# GatewayLoRa0.net
KiCad netlist of a schematic drawn in Altium Designer
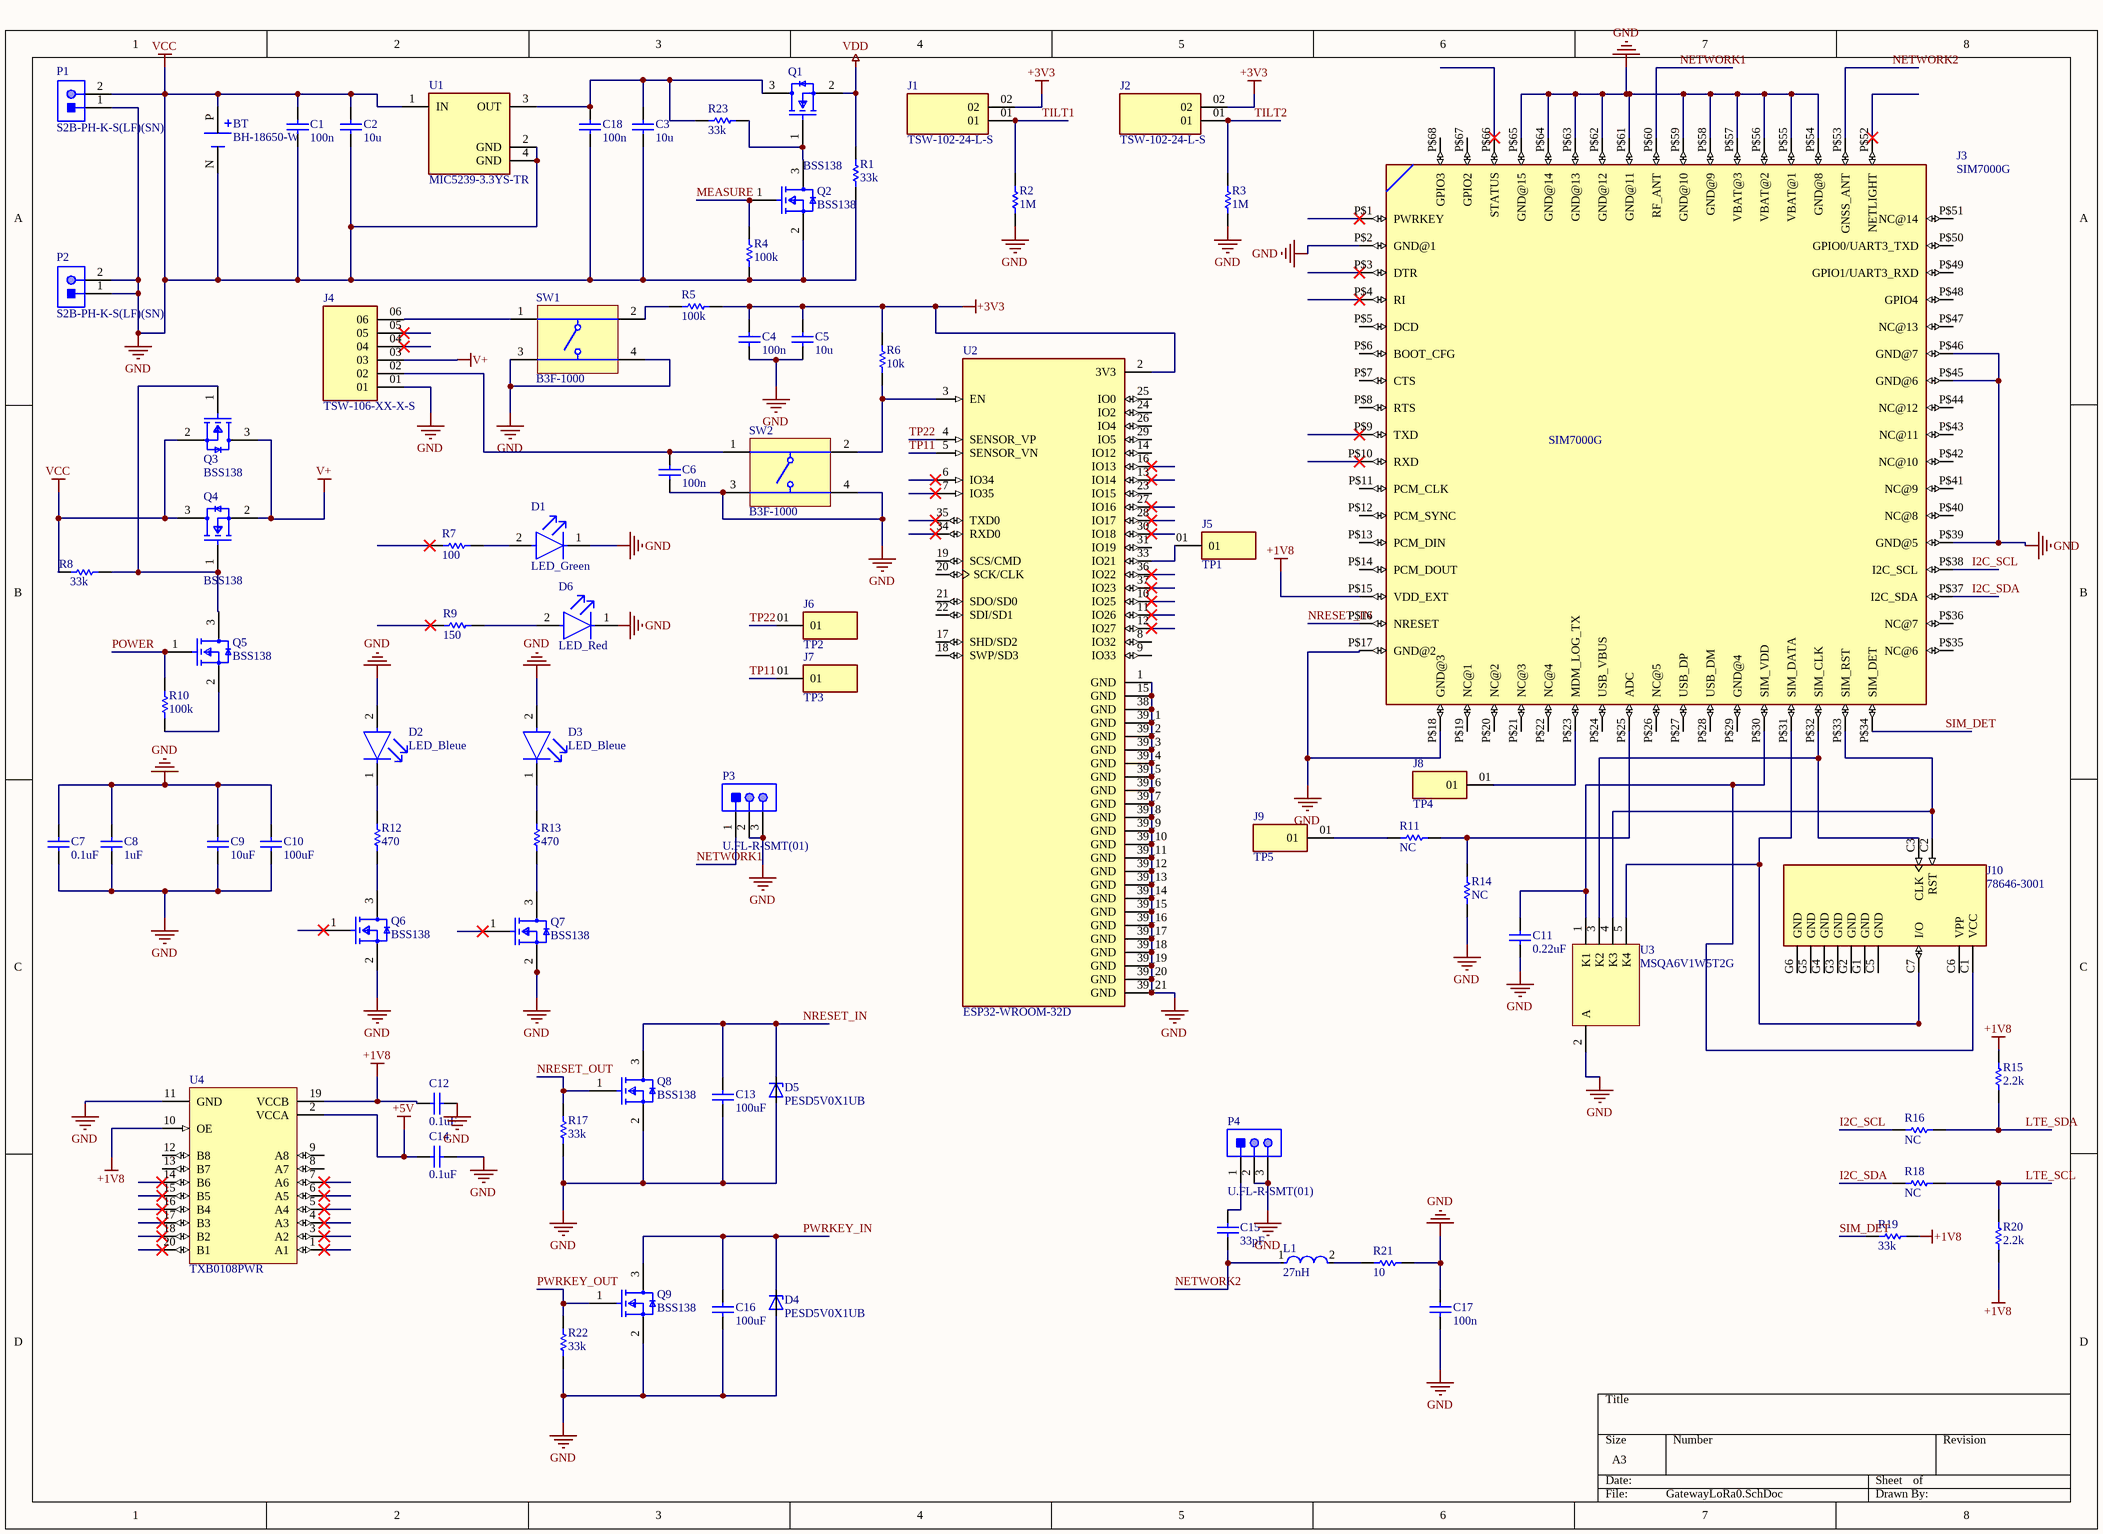
[diagram p0: GatewayLoRa0.SchDoc]

(export (version "E")
  (design (tool "Eeschema 10.0.6"))
  (components
    (comp (ref "BT")
      (value "BH-18650-W")
      (footprint "BAT_BH-18650-W")
      (description "BATTERY HOLDER 18650 6 LEADS")
      (fields (field (name "MF") "MPD"))
      (libsource (lib "BH-18650-W") (part "BH-18650-W"))
    )
    (comp (ref "C1")
      (value "100n")
      (footprint "CAPC1210(3225)280_L")
      (description "CAP 22uF 10V ±10% 1210 (3225 Metric) Thickness 2.8mm SMD")
      (fields (field (name "TOLERANCE") "Â±10%"))
      (libsource (lib "Altium Content Vault") (part "CAP"))
    )
    (comp (ref "C2")
      (value "10u")
      (footprint "CAPC1210(3225)280_L")
      (description "CAP 22uF 10V ±10% 1210 (3225 Metric) Thickness 2.8mm SMD")
      (fields (field (name "TOLERANCE") "Â±10%"))
      (libsource (lib "Altium Content Vault") (part "CAP"))
    )
    (comp (ref "C3")
      (value "10u")
      (footprint "CAPC1210(3225)280_L")
      (description "CAP 22uF 10V ±10% 1210 (3225 Metric) Thickness 2.8mm SMD")
      (fields (field (name "TOLERANCE") "Â±10%"))
      (libsource (lib "Altium Content Vault") (part "CAP"))
    )
    (comp (ref "C4")
      (value "100n")
      (footprint "CAPC1210(3225)280_L")
      (description "CAP 22uF 10V ±10% 1210 (3225 Metric) Thickness 2.8mm SMD")
      (fields (field (name "TOLERANCE") "Â±10%"))
      (libsource (lib "Altium Content Vault") (part "CAP"))
    )
    (comp (ref "C5")
      (value "10u")
      (footprint "CAPC1210(3225)280_L")
      (description "CAP 22uF 10V ±10% 1210 (3225 Metric) Thickness 2.8mm SMD")
      (fields (field (name "TOLERANCE") "Â±10%"))
      (libsource (lib "Altium Content Vault") (part "CAP"))
    )
    (comp (ref "C6")
      (value "100n")
      (footprint "CAPC1210(3225)280_L")
      (description "CAP 22uF 10V ±10% 1210 (3225 Metric) Thickness 2.8mm SMD")
      (fields (field (name "TOLERANCE") "Â±10%"))
      (libsource (lib "Altium Content Vault") (part "CAP"))
    )
    (comp (ref "C7")
      (value "0.1uF")
      (footprint "CAPC1210(3225)280_L")
      (description "CAP 22uF 10V ±10% 1210 (3225 Metric) Thickness 2.8mm SMD")
      (fields (field (name "TOLERANCE") "Â±10%"))
      (libsource (lib "Altium Content Vault") (part "CAP"))
    )
    (comp (ref "C8")
      (value "1uF")
      (footprint "CAPC1210(3225)280_L")
      (description "CAP 22uF 10V ±10% 1210 (3225 Metric) Thickness 2.8mm SMD")
      (fields (field (name "TOLERANCE") "Â±10%"))
      (libsource (lib "Altium Content Vault") (part "CAP"))
    )
    (comp (ref "C9")
      (value "10uF")
      (footprint "CAPC1210(3225)280_L")
      (description "CAP 22uF 10V ±10% 1210 (3225 Metric) Thickness 2.8mm SMD")
      (fields (field (name "TOLERANCE") "Â±10%"))
      (libsource (lib "Altium Content Vault") (part "CAP"))
    )
    (comp (ref "C10")
      (value "100uF")
      (footprint "CAPC1210(3225)280_L")
      (description "CAP 22uF 10V ±10% 1210 (3225 Metric) Thickness 2.8mm SMD")
      (fields (field (name "TOLERANCE") "Â±10%"))
      (libsource (lib "Altium Content Vault") (part "CAP"))
    )
    (comp (ref "C11")
      (value "0.22uF")
      (footprint "CAPC1210(3225)280_L")
      (description "CAP 22uF 10V ±10% 1210 (3225 Metric) Thickness 2.8mm SMD")
      (fields (field (name "TOLERANCE") "Â±10%"))
      (libsource (lib "Altium Content Vault") (part "CAP"))
    )
    (comp (ref "C12")
      (value "0.1uF")
      (footprint "CAPC1210(3225)280_L")
      (description "CAP 22uF 10V ±10% 1210 (3225 Metric) Thickness 2.8mm SMD")
      (fields (field (name "TOLERANCE") "Â±10%"))
      (libsource (lib "Altium Content Vault") (part "CAP"))
    )
    (comp (ref "C13")
      (value "100uF")
      (footprint "CAPC1210(3225)280_L")
      (description "CAP 22uF 10V ±10% 1210 (3225 Metric) Thickness 2.8mm SMD")
      (fields (field (name "TOLERANCE") "Â±10%"))
      (libsource (lib "Altium Content Vault") (part "CAP"))
    )
    (comp (ref "C14")
      (value "0.1uF")
      (footprint "CAPC1210(3225)280_L")
      (description "CAP 22uF 10V ±10% 1210 (3225 Metric) Thickness 2.8mm SMD")
      (fields (field (name "TOLERANCE") "Â±10%"))
      (libsource (lib "Altium Content Vault") (part "CAP"))
    )
    (comp (ref "C15")
      (value "33pF")
      (footprint "CAPC1210(3225)280_L")
      (description "CAP 22uF 10V ±10% 1210 (3225 Metric) Thickness 2.8mm SMD")
      (fields (field (name "TOLERANCE") "Â±10%"))
      (libsource (lib "Altium Content Vault") (part "CAP"))
    )
    (comp (ref "C16")
      (value "100uF")
      (footprint "CAPC1210(3225)280_L")
      (description "CAP 22uF 10V ±10% 1210 (3225 Metric) Thickness 2.8mm SMD")
      (fields (field (name "TOLERANCE") "Â±10%"))
      (libsource (lib "Altium Content Vault") (part "CAP"))
    )
    (comp (ref "C17")
      (value "100n")
      (footprint "CAPC1210(3225)280_L")
      (description "CAP 22uF 10V ±10% 1210 (3225 Metric) Thickness 2.8mm SMD")
      (fields (field (name "TOLERANCE") "Â±10%"))
      (libsource (lib "Altium Content Vault") (part "CAP"))
    )
    (comp (ref "C18")
      (value "100n")
      (footprint "CAPC1210(3225)280_L")
      (description "CAP 22uF 10V ±10% 1210 (3225 Metric) Thickness 2.8mm SMD")
      (fields (field (name "TOLERANCE") "Â±10%"))
      (libsource (lib "Altium Content Vault") (part "CAP"))
    )
    (comp (ref "D1")
      (value "LED_Green")
      (footprint "FP-LTST-C191KGKT-MFG")
      (description "LED GREEN CLEAR SMD")
      (libsource (lib "Altium Content Vault") (part "8706943c75ba83719d021d2fdc84c58"))
    )
    (comp (ref "D2")
      (value "LED_Bleue")
      (footprint "FP-LTST-C193TBKT-5A-MFG")
      (description "LED BLUE CLEAR CHIP SMD")
      (libsource (lib "Altium Content Vault") (part "8706943c75ba83719d021d2fdc84c58"))
    )
    (comp (ref "D3")
      (value "LED_Bleue")
      (footprint "FP-LTST-C193TBKT-5A-MFG")
      (description "LED BLUE CLEAR CHIP SMD")
      (libsource (lib "Altium Content Vault") (part "8706943c75ba83719d021d2fdc84c58"))
    )
    (comp (ref "D4")
      (value "PESD5V0X1UB")
      (footprint "SOD523")
      (description "8V _Typ_ Clamp 1.5A _8/20Âµs_ Ipp Tvs Diode Surface Mount SOD-523")
      (fields (field (name "MF") "NXP Semiconductors"))
      (libsource (lib "PESD5V0X1UB") (part "PESD5V0X1UB"))
    )
    (comp (ref "D5")
      (value "PESD5V0X1UB")
      (footprint "SOD523")
      (description "8V _Typ_ Clamp 1.5A _8/20Âµs_ Ipp Tvs Diode Surface Mount SOD-523")
      (fields (field (name "MF") "NXP Semiconductors"))
      (libsource (lib "PESD5V0X1UB") (part "PESD5V0X1UB"))
    )
    (comp (ref "D6")
      (value "LED_Red")
      (footprint "FP-SML-P11UTT86-MFG")
      (description "LED RED CLEAR 1006 SMD")
      (libsource (lib "Altium Content Vault") (part "8706943c75ba83719d021d2fdc84c58"))
    )
    (comp (ref "J1")
      (value "TSW-102-24-L-S")
      (footprint "SAMTEC_TSW-102-24-L-S")
      (description "Connector Header Through Hole 2 position 0.100 (2.54mm)")
      (fields (field (name "MF") "Samtec"))
      (libsource (lib "TSW-102-24-L-S") (part "TSW-102-24-L-S"))
    )
    (comp (ref "J2")
      (value "TSW-102-24-L-S")
      (footprint "SAMTEC_TSW-102-24-L-S")
      (description "Connector Header Through Hole 2 position 0.100 (2.54mm)")
      (fields (field (name "MF") "Samtec"))
      (libsource (lib "TSW-102-24-L-S") (part "TSW-102-24-L-S"))
    )
    (comp (ref "J3")
      (value "SIM7000G")
      (footprint "SIM7000G")
      (fields (field (name "MF") "SIMCom Wireless Solutions Limited"))
      (libsource (lib "SIM7000G") (part "SIM7000G"))
    )
    (comp (ref "J4")
      (value "TSW-106-XX-X-S")
      (footprint "SAMTEC_TSW-106-XX-X-S")
      (description "TSW - Samtec 2.54mm Pin Header 10.92mm Overall Pin Length (07) - Fast Stock")
      (fields (field (name "MF") "Samtec Inc."))
      (libsource (lib "TSW-106-XX-X-S") (part "TSW-106-XX-X-S"))
    )
    (comp (ref "J5")
      (value "TP1")
      (footprint "SAMTEC_TSW-101-07-L-S")
      (fields (field (name "MF") "Samtec Inc.") (field (name "MP") "TSW-101-07-L-S"))
      (libsource (lib "TSW-101-07-L-S") (part "TSW-101-07-L-S"))
    )
    (comp (ref "J6")
      (value "TP2")
      (footprint "SAMTEC_TSW-101-07-L-S")
      (fields (field (name "MF") "Samtec Inc.") (field (name "MP") "TSW-101-07-L-S"))
      (libsource (lib "TSW-101-07-L-S") (part "TSW-101-07-L-S"))
    )
    (comp (ref "J7")
      (value "TP3")
      (footprint "SAMTEC_TSW-101-07-L-S")
      (fields (field (name "MF") "Samtec Inc.") (field (name "MP") "TSW-101-07-L-S"))
      (libsource (lib "TSW-101-07-L-S") (part "TSW-101-07-L-S"))
    )
    (comp (ref "J8")
      (value "TP4")
      (footprint "SAMTEC_TSW-101-07-L-S")
      (fields (field (name "MF") "Samtec Inc.") (field (name "MP") "TSW-101-07-L-S"))
      (libsource (lib "") (part "TSW-101-07-L-S_1"))
    )
    (comp (ref "J9")
      (value "TP5")
      (footprint "SAMTEC_TSW-101-07-L-S")
      (fields (field (name "MF") "Samtec Inc.") (field (name "MP") "TSW-101-07-L-S"))
      (libsource (lib "") (part "TSW-101-07-L-S_1"))
    )
    (comp (ref "J10")
      (value "78646-3001")
      (footprint "MOLEX_78646-3001")
      (description "6 Position Card Connector Micro SIM Surface Mount, Right Angle Gold")
      (fields (field (name "MF") "Molex"))
      (libsource (lib "78646-3001") (part "78646-3001"))
    )
    (comp (ref "L1")
      (value "27nH")
      (footprint "FP-LQM21PH_G0-IPC_C")
      (description "Multilayer Type Inductor for Power Lines, 0805 (2012), 1μH, 30%, 0.0825Ω, 1.3A")
      (fields (field (name "TOLERANCE") "30%"))
      (libsource (lib "Altium Content Vault") (part "725321dda6339637d4d059423bc1c3c"))
    )
    (comp (ref "P1")
      (value "S2B-PH-K-S(LF)(SN)")
      (footprint "JST-S2B-PH-K-S_V")
      (fields (field (name "TOLERANCE") "20%"))
      (libsource (lib "Altium Content Vault") (part "CN-1P-M-R2"))
    )
    (comp (ref "P2")
      (value "S2B-PH-K-S(LF)(SN)")
      (footprint "JST-S2B-PH-K-S_V")
      (fields (field (name "TOLERANCE") "20%"))
      (libsource (lib "Altium Content Vault") (part "CN-1P-M-R2"))
    )
    (comp (ref "P3")
      (value "U.FL-R-SMT(01)")
      (footprint "HRS-U.FL-R-SMT(10)_V")
      (description "CONN RECPT ULTRA-MINI COAX SMD")
      (fields (field (name "MANUFACTURER") "Hirose Electric") (field (name "APPROVAL CATEGORY") "UL94V-0"))
      (libsource (lib "Altium Content Vault") (part "CN-1P-M-R3"))
    )
    (comp (ref "P4")
      (value "U.FL-R-SMT(01)")
      (footprint "HRS-U.FL-R-SMT(10)_V")
      (description "CONN RECPT ULTRA-MINI COAX SMD")
      (fields (field (name "MANUFACTURER") "Hirose Electric") (field (name "APPROVAL CATEGORY") "UL94V-0"))
      (libsource (lib "Altium Content Vault") (part "CN-1P-M-R3"))
    )
    (comp (ref "Q1")
      (value "BSS138")
      (footprint "FP-318-08-IPC_B")
      (description "MOSFET N-CH 50V 220MA SOT-23")
      (libsource (lib "Altium Content Vault") (part "3b9c635fedb024a5347a57b145af9cc"))
    )
    (comp (ref "Q2")
      (value "BSS138")
      (footprint "FP-318-08-IPC_B")
      (description "MOSFET N-CH 50V 220MA SOT-23")
      (libsource (lib "Altium Content Vault") (part "3b9c635fedb024a5347a57b145af9cc"))
    )
    (comp (ref "Q3")
      (value "BSS138")
      (footprint "FP-318-08-IPC_B")
      (description "MOSFET N-CH 50V 220MA SOT-23")
      (libsource (lib "Altium Content Vault") (part "3b9c635fedb024a5347a57b145af9cc"))
    )
    (comp (ref "Q4")
      (value "BSS138")
      (footprint "FP-318-08-IPC_B")
      (description "MOSFET N-CH 50V 220MA SOT-23")
      (libsource (lib "Altium Content Vault") (part "3b9c635fedb024a5347a57b145af9cc"))
    )
    (comp (ref "Q5")
      (value "BSS138")
      (footprint "FP-318-08-IPC_B")
      (description "MOSFET N-CH 50V 220MA SOT-23")
      (libsource (lib "Altium Content Vault") (part "3b9c635fedb024a5347a57b145af9cc"))
    )
    (comp (ref "Q6")
      (value "BSS138")
      (footprint "FP-318-08-IPC_B")
      (description "MOSFET N-CH 50V 220MA SOT-23")
      (libsource (lib "Altium Content Vault") (part "3b9c635fedb024a5347a57b145af9cc"))
    )
    (comp (ref "Q7")
      (value "BSS138")
      (footprint "FP-318-08-IPC_B")
      (description "MOSFET N-CH 50V 220MA SOT-23")
      (libsource (lib "Altium Content Vault") (part "3b9c635fedb024a5347a57b145af9cc"))
    )
    (comp (ref "Q8")
      (value "BSS138")
      (footprint "FP-318-08-IPC_B")
      (description "MOSFET N-CH 50V 220MA SOT-23")
      (libsource (lib "Altium Content Vault") (part "3b9c635fedb024a5347a57b145af9cc"))
    )
    (comp (ref "Q9")
      (value "BSS138")
      (footprint "FP-318-08-IPC_B")
      (description "MOSFET N-CH 50V 220MA SOT-23")
      (libsource (lib "Altium Content Vault") (part "3b9c635fedb024a5347a57b145af9cc"))
    )
    (comp (ref "R1")
      (value "33k")
      (footprint "RESC3216X60X45LL10T20")
      (fields (field (name "MANUFACTURER") "Vishay Dale") (field (name "PART NUMBER") "CRCW120651R0FKEA"))
      (libsource (lib "Altium Content Vault") (part "RES"))
    )
    (comp (ref "R2")
      (value "1M")
      (footprint "RESC3216X60X45LL10T20")
      (fields (field (name "MANUFACTURER") "Vishay Dale") (field (name "PART NUMBER") "CRCW120651R0FKEA"))
      (libsource (lib "Altium Content Vault") (part "RES"))
    )
    (comp (ref "R3")
      (value "1M")
      (footprint "RESC3216X60X45LL10T20")
      (fields (field (name "MANUFACTURER") "Vishay Dale") (field (name "PART NUMBER") "CRCW120651R0FKEA"))
      (libsource (lib "Altium Content Vault") (part "RES"))
    )
    (comp (ref "R4")
      (value "100k")
      (footprint "RESC3216X60X45LL10T20")
      (fields (field (name "MANUFACTURER") "Vishay Dale") (field (name "PART NUMBER") "CRCW120651R0FKEA"))
      (libsource (lib "Altium Content Vault") (part "RES"))
    )
    (comp (ref "R5")
      (value "100k")
      (footprint "RESC3216X60X45LL10T20")
      (fields (field (name "MANUFACTURER") "Vishay Dale") (field (name "PART NUMBER") "CRCW120651R0FKEA"))
      (libsource (lib "Altium Content Vault") (part "RES"))
    )
    (comp (ref "R6")
      (value "10k")
      (footprint "RESC3216X60X45LL10T20")
      (fields (field (name "MANUFACTURER") "Vishay Dale") (field (name "PART NUMBER") "CRCW120651R0FKEA"))
      (libsource (lib "Altium Content Vault") (part "RES"))
    )
    (comp (ref "R7")
      (value "100")
      (footprint "RESC3216X60X45LL10T20")
      (fields (field (name "MANUFACTURER") "Vishay Dale") (field (name "PART NUMBER") "CRCW120651R0FKEA"))
      (libsource (lib "Altium Content Vault") (part "RES"))
    )
    (comp (ref "R8")
      (value "33k")
      (footprint "RESC3216X60X45LL10T20")
      (fields (field (name "MANUFACTURER") "Vishay Dale") (field (name "PART NUMBER") "CRCW120651R0FKEA"))
      (libsource (lib "Altium Content Vault") (part "RES"))
    )
    (comp (ref "R9")
      (value "150")
      (footprint "RESC3216X60X45LL10T20")
      (fields (field (name "MANUFACTURER") "Vishay Dale") (field (name "PART NUMBER") "CRCW120651R0FKEA"))
      (libsource (lib "Altium Content Vault") (part "RES"))
    )
    (comp (ref "R10")
      (value "100k")
      (footprint "RESC3216X60X45LL10T20")
      (fields (field (name "MANUFACTURER") "Vishay Dale") (field (name "PART NUMBER") "CRCW120651R0FKEA"))
      (libsource (lib "Altium Content Vault") (part "RES"))
    )
    (comp (ref "R11")
      (value "NC")
      (footprint "RESC3216X60X45LL10T20")
      (fields (field (name "MANUFACTURER") "Vishay Dale") (field (name "PART NUMBER") "CRCW120651R0FKEA"))
      (libsource (lib "Altium Content Vault") (part "RES"))
    )
    (comp (ref "R12")
      (value "470")
      (footprint "RESC3216X60X45LL10T20")
      (fields (field (name "MANUFACTURER") "Vishay Dale") (field (name "PART NUMBER") "CRCW120651R0FKEA"))
      (libsource (lib "Altium Content Vault") (part "RES"))
    )
    (comp (ref "R13")
      (value "470")
      (footprint "RESC3216X60X45LL10T20")
      (fields (field (name "MANUFACTURER") "Vishay Dale") (field (name "PART NUMBER") "CRCW120651R0FKEA"))
      (libsource (lib "Altium Content Vault") (part "RES"))
    )
    (comp (ref "R14")
      (value "NC")
      (footprint "RESC3216X60X45LL10T20")
      (fields (field (name "MANUFACTURER") "Vishay Dale") (field (name "PART NUMBER") "CRCW120651R0FKEA"))
      (libsource (lib "Altium Content Vault") (part "RES"))
    )
    (comp (ref "R15")
      (value "2.2k")
      (footprint "RESC3216X60X45LL10T20")
      (fields (field (name "MANUFACTURER") "Vishay Dale") (field (name "PART NUMBER") "CRCW120651R0FKEA"))
      (libsource (lib "Altium Content Vault") (part "RES"))
    )
    (comp (ref "R16")
      (value "NC")
      (footprint "RESC3216X60X45LL10T20")
      (fields (field (name "MANUFACTURER") "Vishay Dale") (field (name "PART NUMBER") "CRCW120651R0FKEA"))
      (libsource (lib "Altium Content Vault") (part "RES"))
    )
    (comp (ref "R17")
      (value "33k")
      (footprint "RESC3216X60X45LL10T20")
      (fields (field (name "MANUFACTURER") "Vishay Dale") (field (name "PART NUMBER") "CRCW120651R0FKEA"))
      (libsource (lib "Altium Content Vault") (part "RES"))
    )
    (comp (ref "R18")
      (value "NC")
      (footprint "RESC3216X60X45LL10T20")
      (fields (field (name "MANUFACTURER") "Vishay Dale") (field (name "PART NUMBER") "CRCW120651R0FKEA"))
      (libsource (lib "Altium Content Vault") (part "RES"))
    )
    (comp (ref "R19")
      (value "33k")
      (footprint "RESC3216X60X45LL10T20")
      (fields (field (name "MANUFACTURER") "Vishay Dale") (field (name "PART NUMBER") "CRCW120651R0FKEA"))
      (libsource (lib "Altium Content Vault") (part "RES"))
    )
    (comp (ref "R20")
      (value "2.2k")
      (footprint "RESC3216X60X45LL10T20")
      (fields (field (name "MANUFACTURER") "Vishay Dale") (field (name "PART NUMBER") "CRCW120651R0FKEA"))
      (libsource (lib "Altium Content Vault") (part "RES"))
    )
    (comp (ref "R21")
      (value "10")
      (footprint "RESC3216X60X45LL10T20")
      (fields (field (name "MANUFACTURER") "Vishay Dale") (field (name "PART NUMBER") "CRCW120651R0FKEA"))
      (libsource (lib "Altium Content Vault") (part "RES"))
    )
    (comp (ref "R22")
      (value "33k")
      (footprint "RESC3216X60X45LL10T20")
      (fields (field (name "MANUFACTURER") "Vishay Dale") (field (name "PART NUMBER") "CRCW120651R0FKEA"))
      (libsource (lib "Altium Content Vault") (part "RES"))
    )
    (comp (ref "R23")
      (value "33k")
      (footprint "RESC3216X60X45LL10T20")
      (fields (field (name "MANUFACTURER") "Vishay Dale") (field (name "PART NUMBER") "CRCW120651R0FKEA"))
      (libsource (lib "Altium Content Vault") (part "RES"))
    )
    (comp (ref "SW1")
      (value "B3F-1000")
      (footprint "OMRON-B3F-1000-4_V")
      (description "Tactile Switch, SPST-NO, 0.05 A, 5 to 24 V, -25 to 70 degC, 4-Pin THD, RoHS, Bulk")
      (libsource (lib "Altium Content Vault") (part "SW-SPST-4_A"))
    )
    (comp (ref "SW2")
      (value "B3F-1000")
      (footprint "OMRON-B3F-1000-4_V")
      (description "Tactile Switch, SPST-NO, 0.05 A, 5 to 24 V, -25 to 70 degC, 4-Pin THD, RoHS, Bulk")
      (libsource (lib "Altium Content Vault") (part "SW-SPST-4_A"))
    )
    (comp (ref "U1")
      (value "MIC5239-3.3YS-TR")
      (footprint "FP-SOT223-3LD-PL-1-MFG")
      (description "IC REG LINEAR 3.3V 500MA SOT223")
      (fields
        (field (name "OCTOPART") "https://octopart.com/mic5239-3.3ys-tr-microchip-66802369")
        (field (name "MANUFACTURER") "Microchip")
      )
      (libsource (lib "Altium Content Vault") (part "ef58ecf1460df94932fa90dd3618f80"))
    )
    (comp (ref "U2")
      (value "ESP32-WROOM-32D")
      (footprint "MODULE_ESP32-WROOM-32D")
      (fields (field (name "MF") "Espressif Systems"))
      (libsource (lib "ESP32-WROOM-32D") (part "ESP32-WROOM-32D"))
    )
    (comp (ref "U3")
      (value "MSQA6V1W5T2G")
      (footprint "ONSC-SC70-5-419A-02_V")
      (description "Quad Array ESD Protection Diodes with Low Clamping Voltage, 5-Pin SC70, Pb-Free, Tape and Reel")
      (fields (field (name "MANUFACTURER") "On Semiconductor"))
      (libsource (lib "Altium Content Vault") (part "ONSC-K1A2K3K4K5-5"))
    )
    (comp (ref "U4")
      (value "TXB0108PWR")
      (footprint "PW0020A_L")
      (fields (field (name "MANUFACTURER") "Texas Instruments"))
      (libsource (lib "Altium Content Vault") (part "TI-TXB0108-PW-20"))
    )
  )
  (nets
    (net (code "1") (name "+1V8") (class "Default")
      (node (ref "C12") (pin "2") (pinfunction "2_2") (pintype "passive"))
      (node (ref "J3") (pin "P$15") (pinfunction "VDD_EXT_P$15") (pintype "bidirectional"))
      (node (ref "R15") (pin "2") (pinfunction "2_2") (pintype "passive"))
      (node (ref "R19") (pin "2") (pinfunction "2_2") (pintype "passive"))
      (node (ref "R20") (pin "1") (pinfunction "1_1") (pintype "passive"))
      (node (ref "U4") (pin "10") (pinfunction "OE_10") (pintype "input"))
      (node (ref "U4") (pin "19") (pinfunction "VCCB_19") (pintype "power_in"))
    )
    (net (code "2") (name "+3V3") (class "Default")
      (node (ref "C4") (pin "2") (pinfunction "2_2") (pintype "passive"))
      (node (ref "C5") (pin "2") (pinfunction "2_2") (pintype "passive"))
      (node (ref "J1") (pin "02") (pinfunction "02_02") (pintype "passive"))
      (node (ref "J2") (pin "02") (pinfunction "02_02") (pintype "passive"))
      (node (ref "R5") (pin "2") (pinfunction "2_2") (pintype "passive"))
      (node (ref "R6") (pin "2") (pinfunction "2_2") (pintype "passive"))
      (node (ref "U2") (pin "2") (pinfunction "3V3_2") (pintype "power_in"))
    )
    (net (code "3") (name "+5V") (class "Default")
      (node (ref "C14") (pin "2") (pinfunction "2_2") (pintype "passive"))
      (node (ref "U4") (pin "2") (pinfunction "VCCA_2") (pintype "power_in"))
    )
    (net (code "4") (name "/I2C_SCL") (class "Default")
      (node (ref "J3") (pin "P$38") (pinfunction "I2C_SCL_P$38") (pintype "bidirectional"))
      (node (ref "R16") (pin "1") (pinfunction "1_1") (pintype "passive"))
    )
    (net (code "5") (name "/I2C_SDA") (class "Default")
      (node (ref "J3") (pin "P$37") (pinfunction "I2C_SDA_P$37") (pintype "bidirectional"))
      (node (ref "R18") (pin "1") (pinfunction "1_1") (pintype "passive"))
    )
    (net (code "6") (name "/LTE_SCL") (class "Default")
      (node (ref "R18") (pin "2") (pinfunction "2_2") (pintype "passive"))
      (node (ref "R20") (pin "2") (pinfunction "2_2") (pintype "passive"))
    )
    (net (code "7") (name "/LTE_SDA") (class "Default")
      (node (ref "R15") (pin "1") (pinfunction "1_1") (pintype "passive"))
      (node (ref "R16") (pin "2") (pinfunction "2_2") (pintype "passive"))
    )
    (net (code "8") (name "/MEASURE") (class "Default")
      (node (ref "Q2") (pin "1") (pinfunction "G_1") (pintype "passive"))
      (node (ref "R4") (pin "2") (pinfunction "2_2") (pintype "passive"))
    )
    (net (code "9") (name "/NETWORK1") (class "Default")
      (node (ref "J3") (pin "P$60") (pinfunction "RF_ANT_P$60") (pintype "bidirectional"))
      (node (ref "P3") (pin "1") (pinfunction "1_1") (pintype "passive"))
    )
    (net (code "10") (name "/NETWORK2") (class "Default")
      (node (ref "C15") (pin "2") (pinfunction "2_2") (pintype "passive"))
      (node (ref "J3") (pin "P$53") (pinfunction "GNSS_ANT_P$53") (pintype "bidirectional"))
      (node (ref "L1") (pin "1") (pinfunction "1_1") (pintype "passive"))
    )
    (net (code "11") (name "/NRESET_IN") (class "Default")
      (node (ref "C13") (pin "1") (pinfunction "1_1") (pintype "passive"))
      (node (ref "D5") (pin "1") (pinfunction "K_1") (pintype "passive"))
      (node (ref "J3") (pin "P$16") (pinfunction "NRESET_P$16") (pintype "bidirectional"))
      (node (ref "Q8") (pin "3") (pinfunction "D_3") (pintype "passive"))
    )
    (net (code "12") (name "/NRESET_OUT") (class "Default")
      (node (ref "Q8") (pin "1") (pinfunction "G_1") (pintype "passive"))
      (node (ref "R17") (pin "2") (pinfunction "2_2") (pintype "passive"))
    )
    (net (code "13") (name "/POWER") (class "Default")
      (node (ref "Q5") (pin "1") (pinfunction "G_1") (pintype "passive"))
      (node (ref "R10") (pin "2") (pinfunction "2_2") (pintype "passive"))
    )
    (net (code "14") (name "/PWRKEY_IN") (class "Default")
      (node (ref "C16") (pin "1") (pinfunction "1_1") (pintype "passive"))
      (node (ref "D4") (pin "1") (pinfunction "K_1") (pintype "passive"))
      (node (ref "Q9") (pin "3") (pinfunction "D_3") (pintype "passive"))
    )
    (net (code "15") (name "/PWRKEY_OUT") (class "Default")
      (node (ref "Q9") (pin "1") (pinfunction "G_1") (pintype "passive"))
      (node (ref "R22") (pin "2") (pinfunction "2_2") (pintype "passive"))
    )
    (net (code "16") (name "/SIM_DET") (class "Default")
      (node (ref "J3") (pin "P$34") (pinfunction "SIM_DET_P$34") (pintype "bidirectional"))
      (node (ref "R19") (pin "1") (pinfunction "1_1") (pintype "passive"))
    )
    (net (code "17") (name "/TILT1") (class "Default")
      (node (ref "J1") (pin "01") (pinfunction "01_01") (pintype "passive"))
      (node (ref "R2") (pin "2") (pinfunction "2_2") (pintype "passive"))
    )
    (net (code "18") (name "/TILT2") (class "Default")
      (node (ref "J2") (pin "01") (pinfunction "01_01") (pintype "passive"))
      (node (ref "R3") (pin "2") (pinfunction "2_2") (pintype "passive"))
    )
    (net (code "19") (name "/TP11") (class "Default")
      (node (ref "J7") (pin "01") (pinfunction "01_01") (pintype "passive"))
      (node (ref "U2") (pin "5") (pinfunction "SENSOR_VN_5") (pintype "input"))
    )
    (net (code "20") (name "/TP22") (class "Default")
      (node (ref "J6") (pin "01") (pinfunction "01_01") (pintype "passive"))
      (node (ref "U2") (pin "4") (pinfunction "SENSOR_VP_4") (pintype "input"))
    )
    (net (code "21") (name "GND") (class "Default")
      (node (ref "BT") (pin "N") (pinfunction "NEG_N") (pintype "passive"))
      (node (ref "BT") (pin "P") (pinfunction "POS_P") (pintype "passive"))
      (node (ref "C1") (pin "1") (pinfunction "1_1") (pintype "passive"))
      (node (ref "C1") (pin "2") (pinfunction "2_2") (pintype "passive"))
      (node (ref "C10") (pin "1") (pinfunction "1_1") (pintype "passive"))
      (node (ref "C10") (pin "2") (pinfunction "2_2") (pintype "passive"))
      (node (ref "C11") (pin "2") (pinfunction "2_2") (pintype "passive"))
      (node (ref "C12") (pin "1") (pinfunction "1_1") (pintype "passive"))
      (node (ref "C13") (pin "2") (pinfunction "2_2") (pintype "passive"))
      (node (ref "C14") (pin "1") (pinfunction "1_1") (pintype "passive"))
      (node (ref "C16") (pin "2") (pinfunction "2_2") (pintype "passive"))
      (node (ref "C17") (pin "1") (pinfunction "1_1") (pintype "passive"))
      (node (ref "C17") (pin "2") (pinfunction "2_2") (pintype "passive"))
      (node (ref "C18") (pin "1") (pinfunction "1_1") (pintype "passive"))
      (node (ref "C2") (pin "1") (pinfunction "1_1") (pintype "passive"))
      (node (ref "C2") (pin "2") (pinfunction "2_2") (pintype "passive"))
      (node (ref "C3") (pin "1") (pinfunction "1_1") (pintype "passive"))
      (node (ref "C4") (pin "1") (pinfunction "1_1") (pintype "passive"))
      (node (ref "C5") (pin "1") (pinfunction "1_1") (pintype "passive"))
      (node (ref "C6") (pin "1") (pinfunction "1_1") (pintype "passive"))
      (node (ref "C7") (pin "1") (pinfunction "1_1") (pintype "passive"))
      (node (ref "C7") (pin "2") (pinfunction "2_2") (pintype "passive"))
      (node (ref "C8") (pin "1") (pinfunction "1_1") (pintype "passive"))
      (node (ref "C8") (pin "2") (pinfunction "2_2") (pintype "passive"))
      (node (ref "C9") (pin "1") (pinfunction "1_1") (pintype "passive"))
      (node (ref "C9") (pin "2") (pinfunction "2_2") (pintype "passive"))
      (node (ref "D1") (pin "1") (pinfunction "C_1") (pintype "passive"))
      (node (ref "D2") (pin "2") (pinfunction "A_2") (pintype "passive"))
      (node (ref "D3") (pin "2") (pinfunction "A_2") (pintype "passive"))
      (node (ref "D4") (pin "2") (pinfunction "A_2") (pintype "passive"))
      (node (ref "D5") (pin "2") (pinfunction "A_2") (pintype "passive"))
      (node (ref "J3") (pin "P$17") (pinfunction "GND@2_P$17") (pintype "bidirectional"))
      (node (ref "J3") (pin "P$18") (pinfunction "GND@3_P$18") (pintype "bidirectional"))
      (node (ref "J3") (pin "P$2") (pinfunction "GND@1_P$2") (pintype "bidirectional"))
      (node (ref "J3") (pin "P$39") (pinfunction "GND@5_P$39") (pintype "bidirectional"))
      (node (ref "J3") (pin "P$45") (pinfunction "GND@6_P$45") (pintype "bidirectional"))
      (node (ref "J3") (pin "P$46") (pinfunction "GND@7_P$46") (pintype "bidirectional"))
      (node (ref "J3") (pin "P$54") (pinfunction "GND@8_P$54") (pintype "bidirectional"))
      (node (ref "J3") (pin "P$55") (pinfunction "VBAT@1_P$55") (pintype "bidirectional"))
      (node (ref "J3") (pin "P$56") (pinfunction "VBAT@2_P$56") (pintype "bidirectional"))
      (node (ref "J3") (pin "P$57") (pinfunction "VBAT@3_P$57") (pintype "bidirectional"))
      (node (ref "J3") (pin "P$58") (pinfunction "GND@9_P$58") (pintype "bidirectional"))
      (node (ref "J3") (pin "P$59") (pinfunction "GND@10_P$59") (pintype "bidirectional"))
      (node (ref "J3") (pin "P$61") (pinfunction "GND@11_P$61") (pintype "bidirectional"))
      (node (ref "J3") (pin "P$62") (pinfunction "GND@12_P$62") (pintype "bidirectional"))
      (node (ref "J3") (pin "P$63") (pinfunction "GND@13_P$63") (pintype "bidirectional"))
      (node (ref "J3") (pin "P$64") (pinfunction "GND@14_P$64") (pintype "bidirectional"))
      (node (ref "J3") (pin "P$65") (pinfunction "GND@15_P$65") (pintype "bidirectional"))
      (node (ref "J4") (pin "01") (pinfunction "01_01") (pintype "passive"))
      (node (ref "P1") (pin "1") (pinfunction "1_1") (pintype "passive"))
      (node (ref "P1") (pin "2") (pinfunction "2_2") (pintype "passive"))
      (node (ref "P2") (pin "1") (pinfunction "1_1") (pintype "passive"))
      (node (ref "P2") (pin "2") (pinfunction "2_2") (pintype "passive"))
      (node (ref "P3") (pin "2") (pinfunction "2_2") (pintype "passive"))
      (node (ref "P3") (pin "3") (pinfunction "3_3") (pintype "passive"))
      (node (ref "P4") (pin "2") (pinfunction "2_2") (pintype "passive"))
      (node (ref "P4") (pin "3") (pinfunction "3_3") (pintype "passive"))
      (node (ref "Q2") (pin "2") (pinfunction "S_2") (pintype "passive"))
      (node (ref "Q3") (pin "2") (pinfunction "S_2") (pintype "passive"))
      (node (ref "Q4") (pin "3") (pinfunction "D_3") (pintype "passive"))
      (node (ref "Q6") (pin "2") (pinfunction "S_2") (pintype "passive"))
      (node (ref "Q7") (pin "2") (pinfunction "S_2") (pintype "passive"))
      (node (ref "Q8") (pin "2") (pinfunction "S_2") (pintype "passive"))
      (node (ref "Q9") (pin "2") (pinfunction "S_2") (pintype "passive"))
      (node (ref "R1") (pin "1") (pinfunction "1_1") (pintype "passive"))
      (node (ref "R14") (pin "1") (pinfunction "1_1") (pintype "passive"))
      (node (ref "R17") (pin "1") (pinfunction "1_1") (pintype "passive"))
      (node (ref "R2") (pin "1") (pinfunction "1_1") (pintype "passive"))
      (node (ref "R21") (pin "2") (pinfunction "2_2") (pintype "passive"))
      (node (ref "R22") (pin "1") (pinfunction "1_1") (pintype "passive"))
      (node (ref "R3") (pin "1") (pinfunction "1_1") (pintype "passive"))
      (node (ref "R4") (pin "1") (pinfunction "1_1") (pintype "passive"))
      (node (ref "R8") (pin "1") (pinfunction "1_1") (pintype "passive"))
      (node (ref "SW1") (pin "3") (pinfunction "3_3") (pintype "passive"))
      (node (ref "SW1") (pin "4") (pinfunction "4_4") (pintype "passive"))
      (node (ref "SW2") (pin "3") (pinfunction "3_3") (pintype "passive"))
      (node (ref "SW2") (pin "4") (pinfunction "4_4") (pintype "passive"))
      (node (ref "U1") (pin "1") (pinfunction "IN_1") (pintype "power_in"))
      (node (ref "U1") (pin "2") (pinfunction "GND_2") (pintype "power_in"))
      (node (ref "U1") (pin "4") (pinfunction "GND_4") (pintype "power_in"))
      (node (ref "U2") (pin "1") (pinfunction "GND_1") (pintype "power_in"))
      (node (ref "U2") (pin "15") (pinfunction "GND_15") (pintype "power_in"))
      (node (ref "U2") (pin "38") (pinfunction "GND_38") (pintype "power_in"))
      (node (ref "U2") (pin "39_1") (pinfunction "GND_39_1") (pintype "power_in"))
      (node (ref "U2") (pin "39_10") (pinfunction "GND_39_10") (pintype "power_in"))
      (node (ref "U2") (pin "39_11") (pinfunction "GND_39_11") (pintype "power_in"))
      (node (ref "U2") (pin "39_12") (pinfunction "GND_39_12") (pintype "power_in"))
      (node (ref "U2") (pin "39_13") (pinfunction "GND_39_13") (pintype "power_in"))
      (node (ref "U2") (pin "39_14") (pinfunction "GND_39_14") (pintype "power_in"))
      (node (ref "U2") (pin "39_15") (pinfunction "GND_39_15") (pintype "power_in"))
      (node (ref "U2") (pin "39_16") (pinfunction "GND_39_16") (pintype "power_in"))
      (node (ref "U2") (pin "39_17") (pinfunction "GND_39_17") (pintype "power_in"))
      (node (ref "U2") (pin "39_18") (pinfunction "GND_39_18") (pintype "power_in"))
      (node (ref "U2") (pin "39_19") (pinfunction "GND_39_19") (pintype "power_in"))
      (node (ref "U2") (pin "39_2") (pinfunction "GND_39_2") (pintype "power_in"))
      (node (ref "U2") (pin "39_20") (pinfunction "GND_39_20") (pintype "power_in"))
      (node (ref "U2") (pin "39_21") (pinfunction "GND_39_21") (pintype "power_in"))
      (node (ref "U2") (pin "39_3") (pinfunction "GND_39_3") (pintype "power_in"))
      (node (ref "U2") (pin "39_4") (pinfunction "GND_39_4") (pintype "power_in"))
      (node (ref "U2") (pin "39_5") (pinfunction "GND_39_5") (pintype "power_in"))
      (node (ref "U2") (pin "39_6") (pinfunction "GND_39_6") (pintype "power_in"))
      (node (ref "U2") (pin "39_7") (pinfunction "GND_39_7") (pintype "power_in"))
      (node (ref "U2") (pin "39_8") (pinfunction "GND_39_8") (pintype "power_in"))
      (node (ref "U2") (pin "39_9") (pinfunction "GND_39_9") (pintype "power_in"))
      (node (ref "U3") (pin "2") (pinfunction "A_2") (pintype "passive"))
      (node (ref "U4") (pin "11") (pinfunction "GND_11") (pintype "power_in"))
    )
    (net (code "22") (name "Net-(C6-Pad2)") (class "Default")
      (node (ref "C6") (pin "2") (pinfunction "2_2") (pintype "passive"))
      (node (ref "J4") (pin "02") (pinfunction "02_02") (pintype "passive"))
      (node (ref "SW2") (pin "1") (pinfunction "1_1") (pintype "passive"))
    )
    (net (code "23") (name "Net-(C15-Pad1)") (class "Default")
      (node (ref "C15") (pin "1") (pinfunction "1_1") (pintype "passive"))
      (node (ref "P4") (pin "1") (pinfunction "1_1") (pintype "passive"))
    )
    (net (code "24") (name "Net-(D1-A)") (class "Default")
      (node (ref "D1") (pin "2") (pinfunction "A_2") (pintype "passive"))
      (node (ref "R7") (pin "2") (pinfunction "2_2") (pintype "passive"))
    )
    (net (code "25") (name "Net-(D2-C)") (class "Default")
      (node (ref "D2") (pin "1") (pinfunction "C_1") (pintype "passive"))
      (node (ref "R12") (pin "2") (pinfunction "2_2") (pintype "passive"))
    )
    (net (code "26") (name "Net-(D3-C)") (class "Default")
      (node (ref "D3") (pin "1") (pinfunction "C_1") (pintype "passive"))
      (node (ref "R13") (pin "2") (pinfunction "2_2") (pintype "passive"))
    )
    (net (code "27") (name "Net-(D6-A)") (class "Default")
      (node (ref "D6") (pin "2") (pinfunction "A_2") (pintype "passive"))
      (node (ref "R9") (pin "2") (pinfunction "2_2") (pintype "passive"))
    )
    (net (code "28") (name "Net-(J3-ADC)") (class "Default")
      (node (ref "J3") (pin "P$25") (pinfunction "ADC_P$25") (pintype "bidirectional"))
      (node (ref "R11") (pin "2") (pinfunction "2_2") (pintype "passive"))
      (node (ref "R14") (pin "2") (pinfunction "2_2") (pintype "passive"))
    )
    (net (code "29") (name "Net-(J3-MDM_LOG_TX)") (class "Default")
      (node (ref "J3") (pin "P$23") (pinfunction "MDM_LOG_TX_P$23") (pintype "bidirectional"))
      (node (ref "J8") (pin "01") (pinfunction "01_01") (pintype "passive"))
    )
    (net (code "30") (name "Net-(J4-Pad06)") (class "Default")
      (node (ref "J4") (pin "06") (pinfunction "06_06") (pintype "passive"))
      (node (ref "SW1") (pin "1") (pinfunction "1_1") (pintype "passive"))
    )
    (net (code "31") (name "Net-(J9-Pad01)") (class "Default")
      (node (ref "J9") (pin "01") (pinfunction "01_01") (pintype "passive"))
      (node (ref "R11") (pin "1") (pinfunction "1_1") (pintype "passive"))
    )
    (net (code "32") (name "Net-(J10-CLK)") (class "Default")
      (node (ref "J10") (pin "C3") (pinfunction "CLK_C3") (pintype "input"))
      (node (ref "J3") (pin "P$32") (pinfunction "SIM_CLK_P$32") (pintype "bidirectional"))
      (node (ref "U3") (pin "3") (pinfunction "K2_3") (pintype "passive"))
    )
    (net (code "33") (name "Net-(J10-I{slash}O)") (class "Default")
      (node (ref "J10") (pin "C7") (pinfunction "I/O_C7") (pintype "bidirectional"))
      (node (ref "J3") (pin "P$31") (pinfunction "SIM_DATA_P$31") (pintype "bidirectional"))
      (node (ref "U3") (pin "5") (pinfunction "K4_5") (pintype "passive"))
    )
    (net (code "34") (name "Net-(J10-RST)") (class "Default")
      (node (ref "J10") (pin "C2") (pinfunction "RST_C2") (pintype "input"))
      (node (ref "J3") (pin "P$33") (pinfunction "SIM_RST_P$33") (pintype "bidirectional"))
      (node (ref "U3") (pin "4") (pinfunction "K3_4") (pintype "passive"))
    )
    (net (code "35") (name "Net-(J10-VCC)") (class "Default")
      (node (ref "C11") (pin "1") (pinfunction "1_1") (pintype "passive"))
      (node (ref "J10") (pin "C1") (pinfunction "VCC_C1") (pintype "power_in"))
      (node (ref "J3") (pin "P$30") (pinfunction "SIM_VDD_P$30") (pintype "bidirectional"))
      (node (ref "U3") (pin "1") (pinfunction "K1_1") (pintype "passive"))
    )
    (net (code "36") (name "Net-(L1-Pad2)") (class "Default")
      (node (ref "L1") (pin "2") (pinfunction "2_2") (pintype "passive"))
      (node (ref "R21") (pin "1") (pinfunction "1_1") (pintype "passive"))
    )
    (net (code "37") (name "Net-(Q1-D)") (class "Default")
      (node (ref "C18") (pin "2") (pinfunction "2_2") (pintype "passive"))
      (node (ref "C3") (pin "2") (pinfunction "2_2") (pintype "passive"))
      (node (ref "Q1") (pin "3") (pinfunction "D_3") (pintype "passive"))
      (node (ref "R23") (pin "1") (pinfunction "1_1") (pintype "passive"))
      (node (ref "U1") (pin "3") (pinfunction "OUT_3") (pintype "power_in"))
    )
    (net (code "38") (name "Net-(Q1-G)") (class "Default")
      (node (ref "Q1") (pin "1") (pinfunction "G_1") (pintype "passive"))
      (node (ref "Q2") (pin "3") (pinfunction "D_3") (pintype "passive"))
      (node (ref "R23") (pin "2") (pinfunction "2_2") (pintype "passive"))
    )
    (net (code "39") (name "Net-(Q3-G)") (class "Default")
      (node (ref "Q3") (pin "1") (pinfunction "G_1") (pintype "passive"))
      (node (ref "Q4") (pin "1") (pinfunction "G_1") (pintype "passive"))
      (node (ref "Q5") (pin "3") (pinfunction "D_3") (pintype "passive"))
      (node (ref "R8") (pin "2") (pinfunction "2_2") (pintype "passive"))
    )
    (net (code "40") (name "Net-(Q5-S)") (class "Default")
      (node (ref "Q5") (pin "2") (pinfunction "S_2") (pintype "passive"))
      (node (ref "R10") (pin "1") (pinfunction "1_1") (pintype "passive"))
    )
    (net (code "41") (name "Net-(Q6-D)") (class "Default")
      (node (ref "Q6") (pin "3") (pinfunction "D_3") (pintype "passive"))
      (node (ref "R12") (pin "1") (pinfunction "1_1") (pintype "passive"))
    )
    (net (code "42") (name "Net-(Q7-D)") (class "Default")
      (node (ref "Q7") (pin "3") (pinfunction "D_3") (pintype "passive"))
      (node (ref "R13") (pin "1") (pinfunction "1_1") (pintype "passive"))
    )
    (net (code "43") (name "Net-(R5-Pad1)") (class "Default")
      (node (ref "R5") (pin "1") (pinfunction "1_1") (pintype "passive"))
      (node (ref "SW1") (pin "2") (pinfunction "2_2") (pintype "passive"))
    )
    (net (code "44") (name "Net-(U2-EN)") (class "Default")
      (node (ref "R6") (pin "1") (pinfunction "1_1") (pintype "passive"))
      (node (ref "SW2") (pin "2") (pinfunction "2_2") (pintype "passive"))
      (node (ref "U2") (pin "3") (pinfunction "EN_3") (pintype "input"))
    )
    (net (code "45") (name "Net-(U2-IO21)") (class "Default")
      (node (ref "J5") (pin "01") (pinfunction "01_01") (pintype "passive"))
      (node (ref "U2") (pin "33") (pinfunction "IO21_33") (pintype "bidirectional"))
    )
    (net (code "46") (name "V+") (class "Default")
      (node (ref "J4") (pin "03") (pinfunction "03_03") (pintype "passive"))
      (node (ref "Q3") (pin "3") (pinfunction "D_3") (pintype "passive"))
      (node (ref "Q4") (pin "2") (pinfunction "S_2") (pintype "passive"))
    )
    (net (code "47") (name "VDD") (class "Default")
      (node (ref "Q1") (pin "2") (pinfunction "S_2") (pintype "passive"))
      (node (ref "R1") (pin "2") (pinfunction "2_2") (pintype "passive"))
    )
    (net (code "48") (name "unconnected-(D6-C-Pad1)") (class "Default")
      (node (ref "D6") (pin "1") (pinfunction "C_1") (pintype "passive"))
    )
    (net (code "49") (name "unconnected-(J3-BOOT_CFG-PadP$6)") (class "Default")
      (node (ref "J3") (pin "P$6") (pinfunction "BOOT_CFG_P$6") (pintype "bidirectional"))
    )
    (net (code "50") (name "unconnected-(J3-CTS-PadP$7)") (class "Default")
      (node (ref "J3") (pin "P$7") (pinfunction "CTS_P$7") (pintype "bidirectional"))
    )
    (net (code "51") (name "unconnected-(J3-DCD-PadP$5)") (class "Default")
      (node (ref "J3") (pin "P$5") (pinfunction "DCD_P$5") (pintype "bidirectional"))
    )
    (net (code "52") (name "unconnected-(J3-DTR-PadP$3)") (class "Default")
      (node (ref "J3") (pin "P$3") (pinfunction "DTR_P$3") (pintype "bidirectional+no_connect"))
    )
    (net (code "53") (name "unconnected-(J3-GND@4-PadP$29)") (class "Default")
      (node (ref "J3") (pin "P$29") (pinfunction "GND@4_P$29") (pintype "bidirectional"))
    )
    (net (code "54") (name "unconnected-(J3-GPIO0{slash}UART3_TXD-PadP$50)") (class "Default")
      (node (ref "J3") (pin "P$50") (pinfunction "GPIO0/UART3_TXD_P$50") (pintype "bidirectional"))
    )
    (net (code "55") (name "unconnected-(J3-GPIO1{slash}UART3_RXD-PadP$49)") (class "Default")
      (node (ref "J3") (pin "P$49") (pinfunction "GPIO1/UART3_RXD_P$49") (pintype "bidirectional"))
    )
    (net (code "56") (name "unconnected-(J3-GPIO2-PadP$67)") (class "Default")
      (node (ref "J3") (pin "P$67") (pinfunction "GPIO2_P$67") (pintype "bidirectional"))
    )
    (net (code "57") (name "unconnected-(J3-GPIO3-PadP$68)") (class "Default")
      (node (ref "J3") (pin "P$68") (pinfunction "GPIO3_P$68") (pintype "bidirectional"))
    )
    (net (code "58") (name "unconnected-(J3-GPIO4-PadP$48)") (class "Default")
      (node (ref "J3") (pin "P$48") (pinfunction "GPIO4_P$48") (pintype "bidirectional"))
    )
    (net (code "59") (name "unconnected-(J3-NC@1-PadP$19)") (class "Default")
      (node (ref "J3") (pin "P$19") (pinfunction "NC@1_P$19") (pintype "bidirectional"))
    )
    (net (code "60") (name "unconnected-(J3-NC@2-PadP$20)") (class "Default")
      (node (ref "J3") (pin "P$20") (pinfunction "NC@2_P$20") (pintype "bidirectional"))
    )
    (net (code "61") (name "unconnected-(J3-NC@3-PadP$21)") (class "Default")
      (node (ref "J3") (pin "P$21") (pinfunction "NC@3_P$21") (pintype "bidirectional"))
    )
    (net (code "62") (name "unconnected-(J3-NC@4-PadP$22)") (class "Default")
      (node (ref "J3") (pin "P$22") (pinfunction "NC@4_P$22") (pintype "bidirectional"))
    )
    (net (code "63") (name "unconnected-(J3-NC@5-PadP$26)") (class "Default")
      (node (ref "J3") (pin "P$26") (pinfunction "NC@5_P$26") (pintype "bidirectional"))
    )
    (net (code "64") (name "unconnected-(J3-NC@6-PadP$35)") (class "Default")
      (node (ref "J3") (pin "P$35") (pinfunction "NC@6_P$35") (pintype "bidirectional"))
    )
    (net (code "65") (name "unconnected-(J3-NC@7-PadP$36)") (class "Default")
      (node (ref "J3") (pin "P$36") (pinfunction "NC@7_P$36") (pintype "bidirectional"))
    )
    (net (code "66") (name "unconnected-(J3-NC@8-PadP$40)") (class "Default")
      (node (ref "J3") (pin "P$40") (pinfunction "NC@8_P$40") (pintype "bidirectional"))
    )
    (net (code "67") (name "unconnected-(J3-NC@9-PadP$41)") (class "Default")
      (node (ref "J3") (pin "P$41") (pinfunction "NC@9_P$41") (pintype "bidirectional"))
    )
    (net (code "68") (name "unconnected-(J3-NC@10-PadP$42)") (class "Default")
      (node (ref "J3") (pin "P$42") (pinfunction "NC@10_P$42") (pintype "bidirectional"))
    )
    (net (code "69") (name "unconnected-(J3-NC@11-PadP$43)") (class "Default")
      (node (ref "J3") (pin "P$43") (pinfunction "NC@11_P$43") (pintype "bidirectional"))
    )
    (net (code "70") (name "unconnected-(J3-NC@12-PadP$44)") (class "Default")
      (node (ref "J3") (pin "P$44") (pinfunction "NC@12_P$44") (pintype "bidirectional"))
    )
    (net (code "71") (name "unconnected-(J3-NC@13-PadP$47)") (class "Default")
      (node (ref "J3") (pin "P$47") (pinfunction "NC@13_P$47") (pintype "bidirectional"))
    )
    (net (code "72") (name "unconnected-(J3-NC@14-PadP$51)") (class "Default")
      (node (ref "J3") (pin "P$51") (pinfunction "NC@14_P$51") (pintype "bidirectional"))
    )
    (net (code "73") (name "unconnected-(J3-NETLIGHT-PadP$52)") (class "Default")
      (node (ref "J3") (pin "P$52") (pinfunction "NETLIGHT_P$52") (pintype "bidirectional+no_connect"))
    )
    (net (code "74") (name "unconnected-(J3-PCM_CLK-PadP$11)") (class "Default")
      (node (ref "J3") (pin "P$11") (pinfunction "PCM_CLK_P$11") (pintype "bidirectional"))
    )
    (net (code "75") (name "unconnected-(J3-PCM_DIN-PadP$13)") (class "Default")
      (node (ref "J3") (pin "P$13") (pinfunction "PCM_DIN_P$13") (pintype "bidirectional"))
    )
    (net (code "76") (name "unconnected-(J3-PCM_DOUT-PadP$14)") (class "Default")
      (node (ref "J3") (pin "P$14") (pinfunction "PCM_DOUT_P$14") (pintype "bidirectional"))
    )
    (net (code "77") (name "unconnected-(J3-PCM_SYNC-PadP$12)") (class "Default")
      (node (ref "J3") (pin "P$12") (pinfunction "PCM_SYNC_P$12") (pintype "bidirectional"))
    )
    (net (code "78") (name "unconnected-(J3-PWRKEY-PadP$1)") (class "Default")
      (node (ref "J3") (pin "P$1") (pinfunction "PWRKEY_P$1") (pintype "bidirectional+no_connect"))
    )
    (net (code "79") (name "unconnected-(J3-RI-PadP$4)") (class "Default")
      (node (ref "J3") (pin "P$4") (pinfunction "RI_P$4") (pintype "bidirectional+no_connect"))
    )
    (net (code "80") (name "unconnected-(J3-RTS-PadP$8)") (class "Default")
      (node (ref "J3") (pin "P$8") (pinfunction "RTS_P$8") (pintype "bidirectional"))
    )
    (net (code "81") (name "unconnected-(J3-RXD-PadP$10)") (class "Default")
      (node (ref "J3") (pin "P$10") (pinfunction "RXD_P$10") (pintype "bidirectional+no_connect"))
    )
    (net (code "82") (name "unconnected-(J3-STATUS-PadP$66)") (class "Default")
      (node (ref "J3") (pin "P$66") (pinfunction "STATUS_P$66") (pintype "bidirectional+no_connect"))
    )
    (net (code "83") (name "unconnected-(J3-TXD-PadP$9)") (class "Default")
      (node (ref "J3") (pin "P$9") (pinfunction "TXD_P$9") (pintype "bidirectional+no_connect"))
    )
    (net (code "84") (name "unconnected-(J3-USB_DM-PadP$28)") (class "Default")
      (node (ref "J3") (pin "P$28") (pinfunction "USB_DM_P$28") (pintype "bidirectional"))
    )
    (net (code "85") (name "unconnected-(J3-USB_DP-PadP$27)") (class "Default")
      (node (ref "J3") (pin "P$27") (pinfunction "USB_DP_P$27") (pintype "bidirectional"))
    )
    (net (code "86") (name "unconnected-(J3-USB_VBUS-PadP$24)") (class "Default")
      (node (ref "J3") (pin "P$24") (pinfunction "USB_VBUS_P$24") (pintype "bidirectional"))
    )
    (net (code "87") (name "unconnected-(J4-Pad04)") (class "Default")
      (node (ref "J4") (pin "04") (pinfunction "04_04") (pintype "passive+no_connect"))
    )
    (net (code "88") (name "unconnected-(J4-Pad05)") (class "Default")
      (node (ref "J4") (pin "05") (pinfunction "05_05") (pintype "passive+no_connect"))
    )
    (net (code "89") (name "unconnected-(J10-GND-PadC5)") (class "Default")
      (node (ref "J10") (pin "C5") (pinfunction "GND_C5") (pintype "power_in"))
    )
    (net (code "90") (name "unconnected-(J10-GND-PadG1)") (class "Default")
      (node (ref "J10") (pin "G1") (pinfunction "GND_G1") (pintype "power_in"))
    )
    (net (code "91") (name "unconnected-(J10-GND-PadG2)") (class "Default")
      (node (ref "J10") (pin "G2") (pinfunction "GND_G2") (pintype "power_in"))
    )
    (net (code "92") (name "unconnected-(J10-GND-PadG3)") (class "Default")
      (node (ref "J10") (pin "G3") (pinfunction "GND_G3") (pintype "power_in"))
    )
    (net (code "93") (name "unconnected-(J10-GND-PadG4)") (class "Default")
      (node (ref "J10") (pin "G4") (pinfunction "GND_G4") (pintype "power_in"))
    )
    (net (code "94") (name "unconnected-(J10-GND-PadG5)") (class "Default")
      (node (ref "J10") (pin "G5") (pinfunction "GND_G5") (pintype "power_in"))
    )
    (net (code "95") (name "unconnected-(J10-GND-PadG6)") (class "Default")
      (node (ref "J10") (pin "G6") (pinfunction "GND_G6") (pintype "power_in"))
    )
    (net (code "96") (name "unconnected-(J10-VPP-PadC6)") (class "Default")
      (node (ref "J10") (pin "C6") (pinfunction "VPP_C6") (pintype "power_in"))
    )
    (net (code "97") (name "unconnected-(Q6-G-Pad1)") (class "Default")
      (node (ref "Q6") (pin "1") (pinfunction "G_1") (pintype "passive+no_connect"))
    )
    (net (code "98") (name "unconnected-(Q7-G-Pad1)") (class "Default")
      (node (ref "Q7") (pin "1") (pinfunction "G_1") (pintype "passive+no_connect"))
    )
    (net (code "99") (name "unconnected-(R7-Pad1)") (class "Default")
      (node (ref "R7") (pin "1") (pinfunction "1_1") (pintype "passive+no_connect"))
    )
    (net (code "100") (name "unconnected-(R9-Pad1)") (class "Default")
      (node (ref "R9") (pin "1") (pinfunction "1_1") (pintype "passive+no_connect"))
    )
    (net (code "101") (name "unconnected-(U2-IO0-Pad25)") (class "Default")
      (node (ref "U2") (pin "25") (pinfunction "IO0_25") (pintype "bidirectional"))
    )
    (net (code "102") (name "unconnected-(U2-IO2-Pad24)") (class "Default")
      (node (ref "U2") (pin "24") (pinfunction "IO2_24") (pintype "bidirectional"))
    )
    (net (code "103") (name "unconnected-(U2-IO4-Pad26)") (class "Default")
      (node (ref "U2") (pin "26") (pinfunction "IO4_26") (pintype "bidirectional"))
    )
    (net (code "104") (name "unconnected-(U2-IO5-Pad29)") (class "Default")
      (node (ref "U2") (pin "29") (pinfunction "IO5_29") (pintype "bidirectional"))
    )
    (net (code "105") (name "unconnected-(U2-IO12-Pad14)") (class "Default")
      (node (ref "U2") (pin "14") (pinfunction "IO12_14") (pintype "bidirectional"))
    )
    (net (code "106") (name "unconnected-(U2-IO13-Pad16)") (class "Default")
      (node (ref "U2") (pin "16") (pinfunction "IO13_16") (pintype "bidirectional+no_connect"))
    )
    (net (code "107") (name "unconnected-(U2-IO14-Pad13)") (class "Default")
      (node (ref "U2") (pin "13") (pinfunction "IO14_13") (pintype "bidirectional+no_connect"))
    )
    (net (code "108") (name "unconnected-(U2-IO15-Pad23)") (class "Default")
      (node (ref "U2") (pin "23") (pinfunction "IO15_23") (pintype "bidirectional"))
    )
    (net (code "109") (name "unconnected-(U2-IO16-Pad27)") (class "Default")
      (node (ref "U2") (pin "27") (pinfunction "IO16_27") (pintype "bidirectional+no_connect"))
    )
    (net (code "110") (name "unconnected-(U2-IO17-Pad28)") (class "Default")
      (node (ref "U2") (pin "28") (pinfunction "IO17_28") (pintype "bidirectional+no_connect"))
    )
    (net (code "111") (name "unconnected-(U2-IO18-Pad30)") (class "Default")
      (node (ref "U2") (pin "30") (pinfunction "IO18_30") (pintype "bidirectional+no_connect"))
    )
    (net (code "112") (name "unconnected-(U2-IO19-Pad31)") (class "Default")
      (node (ref "U2") (pin "31") (pinfunction "IO19_31") (pintype "bidirectional"))
    )
    (net (code "113") (name "unconnected-(U2-IO22-Pad36)") (class "Default")
      (node (ref "U2") (pin "36") (pinfunction "IO22_36") (pintype "bidirectional+no_connect"))
    )
    (net (code "114") (name "unconnected-(U2-IO23-Pad37)") (class "Default")
      (node (ref "U2") (pin "37") (pinfunction "IO23_37") (pintype "bidirectional+no_connect"))
    )
    (net (code "115") (name "unconnected-(U2-IO25-Pad10)") (class "Default")
      (node (ref "U2") (pin "10") (pinfunction "IO25_10") (pintype "bidirectional+no_connect"))
    )
    (net (code "116") (name "unconnected-(U2-IO26-Pad11)") (class "Default")
      (node (ref "U2") (pin "11") (pinfunction "IO26_11") (pintype "bidirectional+no_connect"))
    )
    (net (code "117") (name "unconnected-(U2-IO27-Pad12)") (class "Default")
      (node (ref "U2") (pin "12") (pinfunction "IO27_12") (pintype "bidirectional+no_connect"))
    )
    (net (code "118") (name "unconnected-(U2-IO32-Pad8)") (class "Default")
      (node (ref "U2") (pin "8") (pinfunction "IO32_8") (pintype "bidirectional"))
    )
    (net (code "119") (name "unconnected-(U2-IO33-Pad9)") (class "Default")
      (node (ref "U2") (pin "9") (pinfunction "IO33_9") (pintype "bidirectional"))
    )
    (net (code "120") (name "unconnected-(U2-IO34-Pad6)") (class "Default")
      (node (ref "U2") (pin "6") (pinfunction "IO34_6") (pintype "input+no_connect"))
    )
    (net (code "121") (name "unconnected-(U2-IO35-Pad7)") (class "Default")
      (node (ref "U2") (pin "7") (pinfunction "IO35_7") (pintype "input+no_connect"))
    )
    (net (code "122") (name "unconnected-(U2-RXD0-Pad34)") (class "Default")
      (node (ref "U2") (pin "34") (pinfunction "RXD0_34") (pintype "bidirectional+no_connect"))
    )
    (net (code "123") (name "unconnected-(U2-SCK{slash}CLK-Pad20)") (class "Default")
      (node (ref "U2") (pin "20") (pinfunction "SCK/CLK_20") (pintype "bidirectional"))
    )
    (net (code "124") (name "unconnected-(U2-SCS{slash}CMD-Pad19)") (class "Default")
      (node (ref "U2") (pin "19") (pinfunction "SCS/CMD_19") (pintype "bidirectional"))
    )
    (net (code "125") (name "unconnected-(U2-SDI{slash}SD1-Pad22)") (class "Default")
      (node (ref "U2") (pin "22") (pinfunction "SDI/SD1_22") (pintype "bidirectional"))
    )
    (net (code "126") (name "unconnected-(U2-SDO{slash}SD0-Pad21)") (class "Default")
      (node (ref "U2") (pin "21") (pinfunction "SDO/SD0_21") (pintype "bidirectional"))
    )
    (net (code "127") (name "unconnected-(U2-SHD{slash}SD2-Pad17)") (class "Default")
      (node (ref "U2") (pin "17") (pinfunction "SHD/SD2_17") (pintype "bidirectional"))
    )
    (net (code "128") (name "unconnected-(U2-SWP{slash}SD3-Pad18)") (class "Default")
      (node (ref "U2") (pin "18") (pinfunction "SWP/SD3_18") (pintype "bidirectional"))
    )
    (net (code "129") (name "unconnected-(U2-TXD0-Pad35)") (class "Default")
      (node (ref "U2") (pin "35") (pinfunction "TXD0_35") (pintype "bidirectional+no_connect"))
    )
    (net (code "130") (name "unconnected-(U4-A1-Pad1)") (class "Default")
      (node (ref "U4") (pin "1") (pinfunction "A1_1") (pintype "bidirectional+no_connect"))
    )
    (net (code "131") (name "unconnected-(U4-A2-Pad3)") (class "Default")
      (node (ref "U4") (pin "3") (pinfunction "A2_3") (pintype "bidirectional+no_connect"))
    )
    (net (code "132") (name "unconnected-(U4-A3-Pad4)") (class "Default")
      (node (ref "U4") (pin "4") (pinfunction "A3_4") (pintype "bidirectional+no_connect"))
    )
    (net (code "133") (name "unconnected-(U4-A4-Pad5)") (class "Default")
      (node (ref "U4") (pin "5") (pinfunction "A4_5") (pintype "bidirectional+no_connect"))
    )
    (net (code "134") (name "unconnected-(U4-A5-Pad6)") (class "Default")
      (node (ref "U4") (pin "6") (pinfunction "A5_6") (pintype "bidirectional+no_connect"))
    )
    (net (code "135") (name "unconnected-(U4-A6-Pad7)") (class "Default")
      (node (ref "U4") (pin "7") (pinfunction "A6_7") (pintype "bidirectional+no_connect"))
    )
    (net (code "136") (name "unconnected-(U4-A7-Pad8)") (class "Default")
      (node (ref "U4") (pin "8") (pinfunction "A7_8") (pintype "bidirectional"))
    )
    (net (code "137") (name "unconnected-(U4-A8-Pad9)") (class "Default")
      (node (ref "U4") (pin "9") (pinfunction "A8_9") (pintype "bidirectional"))
    )
    (net (code "138") (name "unconnected-(U4-B1-Pad20)") (class "Default")
      (node (ref "U4") (pin "20") (pinfunction "B1_20") (pintype "bidirectional+no_connect"))
    )
    (net (code "139") (name "unconnected-(U4-B2-Pad18)") (class "Default")
      (node (ref "U4") (pin "18") (pinfunction "B2_18") (pintype "bidirectional+no_connect"))
    )
    (net (code "140") (name "unconnected-(U4-B3-Pad17)") (class "Default")
      (node (ref "U4") (pin "17") (pinfunction "B3_17") (pintype "bidirectional+no_connect"))
    )
    (net (code "141") (name "unconnected-(U4-B4-Pad16)") (class "Default")
      (node (ref "U4") (pin "16") (pinfunction "B4_16") (pintype "bidirectional+no_connect"))
    )
    (net (code "142") (name "unconnected-(U4-B5-Pad15)") (class "Default")
      (node (ref "U4") (pin "15") (pinfunction "B5_15") (pintype "bidirectional+no_connect"))
    )
    (net (code "143") (name "unconnected-(U4-B6-Pad14)") (class "Default")
      (node (ref "U4") (pin "14") (pinfunction "B6_14") (pintype "bidirectional+no_connect"))
    )
    (net (code "144") (name "unconnected-(U4-B7-Pad13)") (class "Default")
      (node (ref "U4") (pin "13") (pinfunction "B7_13") (pintype "bidirectional"))
    )
    (net (code "145") (name "unconnected-(U4-B8-Pad12)") (class "Default")
      (node (ref "U4") (pin "12") (pinfunction "B8_12") (pintype "bidirectional"))
    )
  )
)
